# Battery_18650_3.net
KiCad netlist of a schematic drawn in EasyEDA Pro
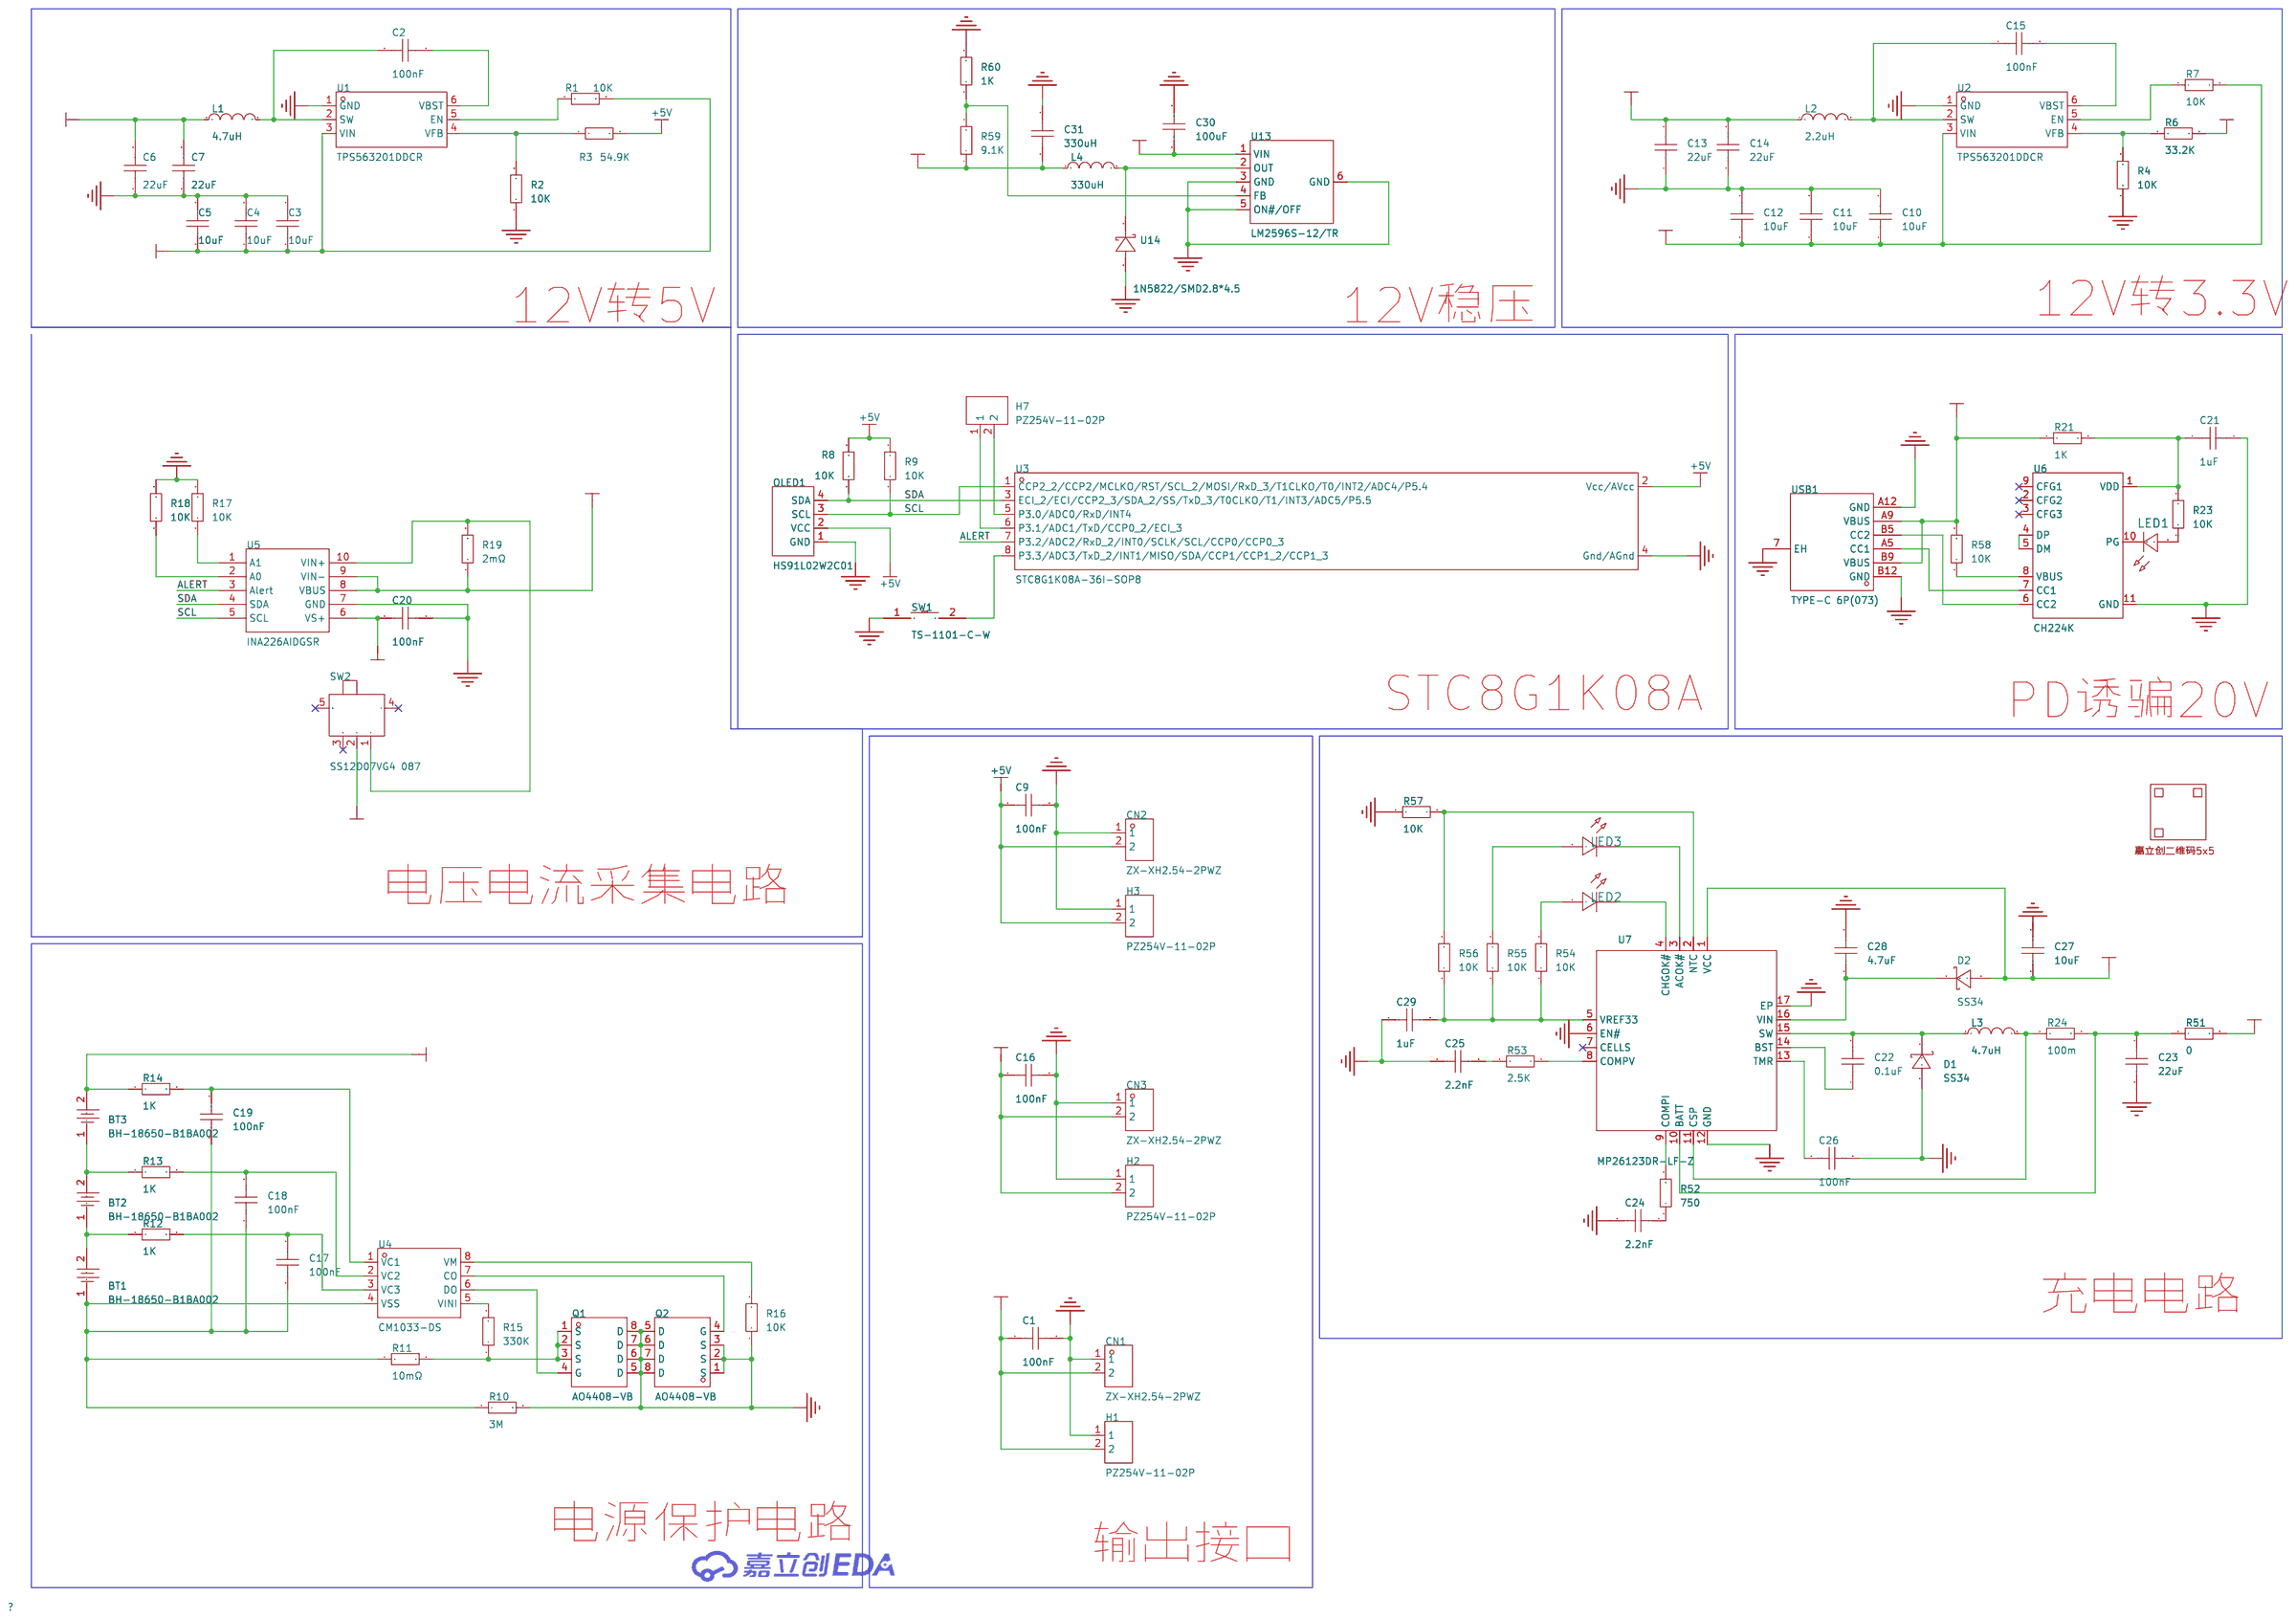
[diagram p0: schematic sheet]

(export (version "E")
  (design (tool "Eeschema 10.0.6"))
  (components
    (comp (ref "BT1")
      (value "BH-18650-B1BA002")
      (footprint "easyedapro:BATTERY-SMD_18650-1S-L77.1-W20.7-1")
      (description "连接器类型:电池盒;适用电池规格:18650;")
      (fields (field (name "Manufacturer") "MYOUNG(美阳)"))
      (libsource (lib "easyedapro") (part "BH-18650-B1BA002"))
    )
    (comp (ref "BT2")
      (value "BH-18650-B1BA002")
      (footprint "easyedapro:BATTERY-SMD_18650-1S-L77.1-W20.7-1")
      (description "连接器类型:电池盒;适用电池规格:18650;")
      (fields (field (name "Manufacturer") "MYOUNG(美阳)"))
      (libsource (lib "easyedapro") (part "BH-18650-B1BA002"))
    )
    (comp (ref "BT3")
      (value "BH-18650-B1BA002")
      (footprint "easyedapro:BATTERY-SMD_18650-1S-L77.1-W20.7-1")
      (description "连接器类型:电池盒;适用电池规格:18650;")
      (fields (field (name "Manufacturer") "MYOUNG(美阳)"))
      (libsource (lib "easyedapro") (part "BH-18650-B1BA002"))
    )
    (comp (ref "C1")
      (value "100nF")
      (footprint "easyedapro:C0603")
      (libsource (lib "easyedapro") (part "CapAcitance"))
    )
    (comp (ref "C2")
      (value "100nF")
      (footprint "easyedapro:C0603")
      (libsource (lib "easyedapro") (part "CapAcitance"))
    )
    (comp (ref "C3")
      (value "10uF")
      (footprint "easyedapro:C0603")
      (libsource (lib "easyedapro") (part "CapAcitance"))
    )
    (comp (ref "C4")
      (value "10uF")
      (footprint "easyedapro:C0603")
      (libsource (lib "easyedapro") (part "CapAcitance"))
    )
    (comp (ref "C5")
      (value "10uF")
      (footprint "easyedapro:C0603")
      (libsource (lib "easyedapro") (part "CapAcitance"))
    )
    (comp (ref "C6")
      (value "22uF")
      (footprint "easyedapro:C0603")
      (libsource (lib "easyedapro") (part "CapAcitance"))
    )
    (comp (ref "C7")
      (value "22uF")
      (footprint "easyedapro:C0603")
      (libsource (lib "easyedapro") (part "CapAcitance"))
    )
    (comp (ref "C9")
      (value "100nF")
      (footprint "easyedapro:C0603")
      (libsource (lib "easyedapro") (part "CapAcitance"))
    )
    (comp (ref "C10")
      (value "10uF")
      (footprint "easyedapro:C0603")
      (libsource (lib "easyedapro") (part "CapAcitance"))
    )
    (comp (ref "C11")
      (value "10uF")
      (footprint "easyedapro:C0603")
      (libsource (lib "easyedapro") (part "CapAcitance"))
    )
    (comp (ref "C12")
      (value "10uF")
      (footprint "easyedapro:C0603")
      (libsource (lib "easyedapro") (part "CapAcitance"))
    )
    (comp (ref "C13")
      (value "22uF")
      (footprint "easyedapro:C0603")
      (libsource (lib "easyedapro") (part "CapAcitance"))
    )
    (comp (ref "C14")
      (value "22uF")
      (footprint "easyedapro:C0603")
      (libsource (lib "easyedapro") (part "CapAcitance"))
    )
    (comp (ref "C15")
      (value "100nF")
      (footprint "easyedapro:C0603")
      (libsource (lib "easyedapro") (part "CapAcitance"))
    )
    (comp (ref "C16")
      (value "100nF")
      (footprint "easyedapro:C0603")
      (libsource (lib "easyedapro") (part "CapAcitance"))
    )
    (comp (ref "C17")
      (value "100nF")
      (footprint "easyedapro:C0603")
      (libsource (lib "easyedapro") (part "CapAcitance"))
    )
    (comp (ref "C18")
      (value "100nF")
      (footprint "easyedapro:C0603")
      (libsource (lib "easyedapro") (part "CapAcitance"))
    )
    (comp (ref "C19")
      (value "100nF")
      (footprint "easyedapro:C0603")
      (libsource (lib "easyedapro") (part "CapAcitance"))
    )
    (comp (ref "C20")
      (value "100nF")
      (footprint "easyedapro:C0603")
      (libsource (lib "easyedapro") (part "CapAcitance"))
    )
    (comp (ref "C21")
      (value "1uF")
      (footprint "easyedapro:C0603")
      (libsource (lib "easyedapro") (part "CapAcitance"))
    )
    (comp (ref "C22")
      (value "0.1uF")
      (footprint "easyedapro:C0603")
      (libsource (lib "easyedapro") (part "CapAcitance"))
    )
    (comp (ref "C23")
      (value "22uF")
      (footprint "easyedapro:C0603")
      (libsource (lib "easyedapro") (part "CapAcitance"))
    )
    (comp (ref "C24")
      (value "2.2nF")
      (footprint "easyedapro:C0603")
      (libsource (lib "easyedapro") (part "CapAcitance"))
    )
    (comp (ref "C25")
      (value "2.2nF")
      (footprint "easyedapro:C0603")
      (libsource (lib "easyedapro") (part "CapAcitance"))
    )
    (comp (ref "C26")
      (value "100nF")
      (footprint "easyedapro:C0603")
      (libsource (lib "easyedapro") (part "CapAcitance"))
    )
    (comp (ref "C27")
      (value "10uF")
      (footprint "easyedapro:C0603")
      (libsource (lib "easyedapro") (part "CapAcitance"))
    )
    (comp (ref "C28")
      (value "4.7uF")
      (footprint "easyedapro:C0603")
      (libsource (lib "easyedapro") (part "CapAcitance"))
    )
    (comp (ref "C29")
      (value "1uF")
      (footprint "easyedapro:C0603")
      (libsource (lib "easyedapro") (part "CapAcitance"))
    )
    (comp (ref "C30")
      (value "100uF")
      (footprint "easyedapro:C0603")
      (libsource (lib "easyedapro") (part "CapAcitance"))
    )
    (comp (ref "C31")
      (value "330uH")
      (footprint "easyedapro:C0603")
      (libsource (lib "easyedapro") (part "CapAcitance"))
    )
    (comp (ref "CN1")
      (value "ZX-XH2.54-2PWZ")
      (footprint "easyedapro:CONN-TH_2P-P2.50_ZX-XH2.54-2PWZ")
      (fields (field (name "Manufacturer") "Megastar(兆星)"))
      (libsource (lib "easyedapro") (part "ZX-XH2.54-2PWZ"))
    )
    (comp (ref "CN2")
      (value "ZX-XH2.54-2PWZ")
      (footprint "easyedapro:CONN-TH_2P-P2.50_ZX-XH2.54-2PWZ")
      (fields (field (name "Manufacturer") "Megastar(兆星)"))
      (libsource (lib "easyedapro") (part "ZX-XH2.54-2PWZ"))
    )
    (comp (ref "CN3")
      (value "ZX-XH2.54-2PWZ")
      (footprint "easyedapro:CONN-TH_2P-P2.50_ZX-XH2.54-2PWZ")
      (fields (field (name "Manufacturer") "Megastar(兆星)"))
      (libsource (lib "easyedapro") (part "ZX-XH2.54-2PWZ"))
    )
    (comp (ref "D1")
      (value "SS34")
      (footprint "easyedapro:SMC_L6.9-W5.9-LS7.9-RD")
      (description "正向压降(Vf):500mV@3A;直流反向耐压(Vr):40V;平均整流电流(Io):3A;")
      (fields (field (name "Manufacturer") "onsemi(安森美)"))
      (libsource (lib "easyedapro") (part "SS34_C154551"))
    )
    (comp (ref "D2")
      (value "SS34")
      (footprint "easyedapro:SMC_L6.9-W5.9-LS7.9-RD")
      (description "正向压降(Vf):500mV@3A;直流反向耐压(Vr):40V;平均整流电流(Io):3A;")
      (fields (field (name "Manufacturer") "onsemi(安森美)"))
      (libsource (lib "easyedapro") (part "SS34_C154551"))
    )
    (comp (ref "H1")
      (value "PZ254V-11-02P")
      (footprint "easyedapro:HDR-TH_2P-P2.54-V-M")
      (fields (field (name "Manufacturer") "XFCN(兴飞)"))
      (libsource (lib "easyedapro") (part "PZ254V-11-02P"))
    )
    (comp (ref "H2")
      (value "PZ254V-11-02P")
      (footprint "easyedapro:HDR-TH_2P-P2.54-V-M")
      (fields (field (name "Manufacturer") "XFCN(兴飞)"))
      (libsource (lib "easyedapro") (part "PZ254V-11-02P"))
    )
    (comp (ref "H3")
      (value "PZ254V-11-02P")
      (footprint "easyedapro:HDR-TH_2P-P2.54-V-M")
      (fields (field (name "Manufacturer") "XFCN(兴飞)"))
      (libsource (lib "easyedapro") (part "PZ254V-11-02P"))
    )
    (comp (ref "H7")
      (value "PZ254V-11-02P")
      (footprint "easyedapro:HDR-TH_2P-P2.54-V-M")
      (fields (field (name "Manufacturer") "XFCN(兴飞)"))
      (libsource (lib "easyedapro") (part "PZ254V-11-02P"))
    )
    (comp (ref "L1")
      (value "4.7uH")
      (footprint "easyedapro:IND-SMD_L4.0-W4.0_FNR40XXS")
      (description "电感值:4.7uH;精度:±20%;额定电流:2.3A;饱和电流(Isat):3.2A;类型:磁胶屏蔽绕线合金电感;")
      (fields (field (name "Manufacturer Part") "FNR4030S4R7MT") (field (name "Manufacturer") "cjiang(长江微电)"))
      (libsource (lib "easyedapro") (part "FNR4030S4R7MT"))
    )
    (comp (ref "L2")
      (value "2.2uH")
      (footprint "easyedapro:IND-SMD_L4.0-W4.0_FNR40XXS")
      (description "电感值:4.7uH;精度:±20%;额定电流:2.3A;饱和电流(Isat):3.2A;类型:磁胶屏蔽绕线合金电感;")
      (fields (field (name "Manufacturer Part") "FNR4030S4R7MT") (field (name "Manufacturer") "cjiang(长江微电)"))
      (libsource (lib "easyedapro") (part "FNR4030S4R7MT"))
    )
    (comp (ref "L3")
      (value "4.7uH")
      (footprint "easyedapro:IND-SMD_L11.5-W10.0_FXL1040")
      (description "电感值:4.7uH;精度:±20%;额定电流:9A;饱和电流(Isat):15A;类型:一体成型电感;")
      (fields (field (name "Manufacturer Part") "FXL1040-4R7-M") (field (name "Manufacturer") "cjiang(长江微电)"))
      (libsource (lib "easyedapro") (part "FXL1040-4R7-M"))
    )
    (comp (ref "L4")
      (value "330uH")
      (footprint "easyedapro:IND-SMD_L11.5-W10.0_FXL1040")
      (description "电感值:4.7uH;精度:±20%;额定电流:9A;饱和电流(Isat):15A;类型:一体成型电感;")
      (fields (field (name "Manufacturer Part") "FXL1040-4R7-M") (field (name "Manufacturer") "cjiang(长江微电)"))
      (libsource (lib "easyedapro") (part "FXL1040-4R7-M"))
    )
    (comp (ref "LED1")
      (value "~")
      (footprint "easyedapro:LED_0603")
      (libsource (lib "easyedapro") (part "LED_R"))
    )
    (comp (ref "LED2")
      (value "~")
      (footprint "easyedapro:LED_0603")
      (libsource (lib "easyedapro") (part "LED_R"))
    )
    (comp (ref "LED3")
      (value "~")
      (footprint "easyedapro:LED_0603")
      (libsource (lib "easyedapro") (part "LED_R"))
    )
    (comp (ref "OLED1")
      (value "HS91L02W2C01")
      (footprint "easyedapro:OLED-TH_L38.0-W12.0_HS91L02W2C01")
      (description "主控芯片:SSD1306;接口类型:I2C;尺寸(inch):0.91;像素分辨率:128x32;")
      (fields (field (name "Manufacturer") "HS(汉昇)"))
      (libsource (lib "easyedapro") (part "HS91L02W2C01"))
    )
    (comp (ref "Q1")
      (value "AO4408-VB")
      (footprint "easyedapro:SO-8_L4.9-W3.9-P1.27-LS5.9-BL")
      (description "类型:1个N沟道;漏源电压(Vdss):20V;连续漏极电流(Id):13A;导通电阻(RDS(on)@Vgs,Id):-;功率:2.2W;阈值电压(Vgs(th)@Id):1V@250uA;")
      (fields (field (name "Manufacturer") "VBsemi(微碧半导体)"))
      (libsource (lib "easyedapro") (part "AO4408"))
    )
    (comp (ref "Q2")
      (value "AO4408-VB")
      (footprint "easyedapro:SO-8_L4.9-W3.9-P1.27-LS5.9-BL")
      (description "类型:1个N沟道;漏源电压(Vdss):20V;连续漏极电流(Id):13A;导通电阻(RDS(on)@Vgs,Id):-;功率:2.2W;阈值电压(Vgs(th)@Id):1V@250uA;")
      (fields (field (name "Manufacturer") "VBsemi(微碧半导体)"))
      (libsource (lib "easyedapro") (part "AO4408"))
    )
    (comp (ref "R1") (value "10K") (footprint "easyedapro:R0603") (libsource (lib "easyedapro") (part "电阻")))
    (comp (ref "R2") (value "10K") (footprint "easyedapro:R0603") (libsource (lib "easyedapro") (part "电阻")))
    (comp (ref "R3")
      (value "54.9K")
      (footprint "easyedapro:R0603")
      (libsource (lib "easyedapro") (part "电阻"))
    )
    (comp (ref "R4") (value "10K") (footprint "easyedapro:R0603") (libsource (lib "easyedapro") (part "电阻")))
    (comp (ref "R6")
      (value "33.2K")
      (footprint "easyedapro:R0603")
      (libsource (lib "easyedapro") (part "电阻"))
    )
    (comp (ref "R7") (value "10K") (footprint "easyedapro:R0603") (libsource (lib "easyedapro") (part "电阻")))
    (comp (ref "R8") (value "10K") (footprint "easyedapro:R0603") (libsource (lib "easyedapro") (part "电阻")))
    (comp (ref "R9") (value "10K") (footprint "easyedapro:R0603") (libsource (lib "easyedapro") (part "电阻")))
    (comp (ref "R10") (value "3M") (footprint "easyedapro:R0603") (libsource (lib "easyedapro") (part "电阻")))
    (comp (ref "R11")
      (value "10mΩ")
      (footprint "easyedapro:R0603")
      (libsource (lib "easyedapro") (part "电阻"))
    )
    (comp (ref "R12") (value "1K") (footprint "easyedapro:R0603") (libsource (lib "easyedapro") (part "电阻")))
    (comp (ref "R13") (value "1K") (footprint "easyedapro:R0603") (libsource (lib "easyedapro") (part "电阻")))
    (comp (ref "R14") (value "1K") (footprint "easyedapro:R0603") (libsource (lib "easyedapro") (part "电阻")))
    (comp (ref "R15")
      (value "330K")
      (footprint "easyedapro:R0603")
      (libsource (lib "easyedapro") (part "电阻"))
    )
    (comp (ref "R16") (value "10K") (footprint "easyedapro:R0603") (libsource (lib "easyedapro") (part "电阻")))
    (comp (ref "R17") (value "10K") (footprint "easyedapro:R0603") (libsource (lib "easyedapro") (part "电阻")))
    (comp (ref "R18") (value "10K") (footprint "easyedapro:R0603") (libsource (lib "easyedapro") (part "电阻")))
    (comp (ref "R19") (value "2mΩ") (footprint "easyedapro:R0603") (libsource (lib "easyedapro") (part "电阻")))
    (comp (ref "R21") (value "1K") (footprint "easyedapro:R0603") (libsource (lib "easyedapro") (part "电阻")))
    (comp (ref "R23") (value "10K") (footprint "easyedapro:R0603") (libsource (lib "easyedapro") (part "电阻")))
    (comp (ref "R24")
      (value "100m")
      (footprint "easyedapro:R0603")
      (libsource (lib "easyedapro") (part "电阻"))
    )
    (comp (ref "R51") (value "0") (footprint "easyedapro:R0603") (libsource (lib "easyedapro") (part "电阻")))
    (comp (ref "R52") (value "750") (footprint "easyedapro:R0603") (libsource (lib "easyedapro") (part "电阻")))
    (comp (ref "R53")
      (value "2.5K")
      (footprint "easyedapro:R0603")
      (libsource (lib "easyedapro") (part "电阻"))
    )
    (comp (ref "R54") (value "10K") (footprint "easyedapro:R0603") (libsource (lib "easyedapro") (part "电阻")))
    (comp (ref "R55") (value "10K") (footprint "easyedapro:R0603") (libsource (lib "easyedapro") (part "电阻")))
    (comp (ref "R56") (value "10K") (footprint "easyedapro:R0603") (libsource (lib "easyedapro") (part "电阻")))
    (comp (ref "R57") (value "10K") (footprint "easyedapro:R0603") (libsource (lib "easyedapro") (part "电阻")))
    (comp (ref "R58") (value "10K") (footprint "easyedapro:R0603") (libsource (lib "easyedapro") (part "电阻")))
    (comp (ref "R59")
      (value "9.1K")
      (footprint "easyedapro:R0603")
      (libsource (lib "easyedapro") (part "电阻"))
    )
    (comp (ref "R60") (value "1K") (footprint "easyedapro:R0603") (libsource (lib "easyedapro") (part "电阻")))
    (comp (ref "SW1")
      (value "TS-1101-C-W")
      (footprint "easyedapro:SW-SMD_L6.0-W3.3-LS8.0")
      (fields (field (name "Manufacturer") "XKB Connectivity(中国星坤)"))
      (libsource (lib "easyedapro") (part "TS-1101-C-W"))
    )
    (comp (ref "SW2")
      (value "SS12D07VG4 087")
      (footprint "easyedapro:SW-TH_SS12D07VG4")
      (description "电路结构:单刀双掷;安装方式:直插;开关颜色:-;额定电流(DC):500mA;额定电压(DC):50V;额定电流(AC):-;额定电压(AC):-;机械寿命:5千次;")
      (fields (field (name "Manufacturer") "SHOU HAN(首韩)"))
      (libsource (lib "easyedapro") (part "SS12D07VG4 087"))
    )
    (comp (ref "U1")
      (value "TPS563201DDCR")
      (footprint "easyedapro:SOT-23-6_L2.9-W1.6-P0.95-LS2.8-BR")
      (description "功能类型:降压型;输出类型:可调;工作电压:4.5V~17V;输出电压:768mV~7V;输出电流:3A;")
      (fields (field (name "Manufacturer") "TI(德州仪器)"))
      (libsource (lib "easyedapro") (part "TPS563201DDCR"))
    )
    (comp (ref "U2")
      (value "TPS563201DDCR")
      (footprint "easyedapro:SOT-23-6_L2.9-W1.6-P0.95-LS2.8-BR")
      (description "功能类型:降压型;输出类型:可调;工作电压:4.5V~17V;输出电压:768mV~7V;输出电流:3A;")
      (fields (field (name "Manufacturer") "TI(德州仪器)"))
      (libsource (lib "easyedapro") (part "TPS563201DDCR"))
    )
    (comp (ref "U3")
      (value "STC8G1K08A-36I-SOP8")
      (footprint "easyedapro:SOP-8_L5.0-W4.0-P1.27-LS6.0-BL")
      (description "CPU内核:51系列;应用领域:-;")
      (fields (field (name "Manufacturer") "STC"))
      (libsource (lib "easyedapro") (part "STC8G1K08A-36I-SOP8"))
    )
    (comp (ref "U4")
      (value "CM1033-DS")
      (footprint "easyedapro:SOP-8_L5.0-W4.0-P1.27-LS6.2-BL")
      (fields (field (name "Manufacturer") "iCM(创芯微)"))
      (libsource (lib "easyedapro") (part "CM1033-DS"))
    )
    (comp (ref "U5")
      (value "INA226AIDGSR")
      (footprint "easyedapro:MSOP-10_L3.0-W3.0-P0.50-LS5.0-BL")
      (description "放大器数:-;共模电压:300mV~40V;增益:-;带宽:-;")
      (fields (field (name "Manufacturer") "TI(德州仪器)"))
      (libsource (lib "easyedapro") (part "INA226AIDGSR"))
    )
    (comp (ref "U6")
      (value "CH224K")
      (footprint "easyedapro:ESSOP-10_L4.9-W3.9-P1.0-LS6.0-TL-EP")
      (fields (field (name "Manufacturer") "WCH(南京沁恒)"))
      (libsource (lib "easyedapro") (part "CH224K"))
    )
    (comp (ref "U7")
      (value "MP26123DR-LF-Z")
      (footprint "easyedapro:QFN-16_L4.0-W4.0-P0.65-BL-EP2.2")
      (description "电源电压:24V;最大充电电流:2A;电池类型:锂离子/聚合物;电池节数:2~3;")
      (fields (field (name "Manufacturer") "MPS(芯源)"))
      (libsource (lib "easyedapro") (part "MP26123DR-LF-Z"))
    )
    (comp (ref "U13")
      (value "LM2596S-12/TR")
      (footprint "easyedapro:TO-263-5_L10.6-W9.6-P1.70-LS15.9-BR")
      (description "功能类型:降压型;工作电压:4.5V~40V;输出电压:11.52V~12.48V;输出电流:3A;")
      (fields (field (name "Manufacturer") "HGC(华冠)"))
      (libsource (lib "easyedapro") (part "LM2596S-12/TR_C462059"))
    )
    (comp (ref "U14")
      (value "1N5822/SMD2.8*4.5")
      (footprint "easyedapro:DO-214AC_L4.3-W2.7-LS5.0-RD")
      (libsource (lib "easyedapro") (part "1N5822/SMD2.8*4.5"))
    )
    (comp (ref "U24")
      (value "~")
      (footprint "easyedapro:JLC-QRCODE-5x5")
      (libsource (lib "easyedapro") (part "嘉立创二维码5x5"))
    )
    (comp (ref "USB1")
      (value "TYPE-C 6P(073)")
      (footprint "easyedapro:TYPE-C-SMD_TYPE-C-6P_5")
      (description "连接器类型:Type-C;标准:USB 3.1;公母:母;安装方式:卧贴;触点数量:6P;端口数量:1;额定电流 - 电源:3A;工作温度范围:-25°C~+85°C;")
      (fields (field (name "Manufacturer") "SHOU HAN(首韩)"))
      (libsource (lib "easyedapro") (part "TYPE-C 6P(073)"))
    )
  )
  (nets
    (net (code "1") (name "+3.3V") (class "Default")
      (node (ref "C13") (pin "2") (pinfunction "2_2") (pintype "input"))
      (node (ref "C14") (pin "2") (pinfunction "2_2") (pintype "input"))
      (node (ref "C16") (pin "1") (pinfunction "1_1") (pintype "input"))
      (node (ref "C20") (pin "1") (pinfunction "1_1") (pintype "input"))
      (node (ref "CN3") (pin "2") (pinfunction "2_2") (pintype "unspecified"))
      (node (ref "H2") (pin "2") (pinfunction "2_2") (pintype "unspecified"))
      (node (ref "L2") (pin "1") (pinfunction "1_1") (pintype "unspecified"))
      (node (ref "R6") (pin "2") (pinfunction "2_2") (pintype "input"))
      (node (ref "U5") (pin "6") (pinfunction "VS+_6") (pintype "unspecified"))
    )
    (net (code "2") (name "+5V") (class "Default")
      (node (ref "C6") (pin "2") (pinfunction "2_2") (pintype "input"))
      (node (ref "C7") (pin "2") (pinfunction "2_2") (pintype "input"))
      (node (ref "C9") (pin "1") (pinfunction "1_1") (pintype "input"))
      (node (ref "CN2") (pin "2") (pinfunction "2_2") (pintype "unspecified"))
      (node (ref "H3") (pin "2") (pinfunction "2_2") (pintype "unspecified"))
      (node (ref "L1") (pin "1") (pinfunction "1_1") (pintype "unspecified"))
      (node (ref "OLED1") (pin "2") (pinfunction "VCC_2") (pintype "unspecified"))
      (node (ref "R3") (pin "2") (pinfunction "2_2") (pintype "input"))
      (node (ref "R8") (pin "2") (pinfunction "2_2") (pintype "input"))
      (node (ref "R9") (pin "1") (pinfunction "1_1") (pintype "input"))
      (node (ref "U3") (pin "2") (pinfunction "Vcc/AVcc_2") (pintype "unspecified"))
    )
    (net (code "3") (name "/ALERT") (class "Default")
      (node (ref "U3") (pin "7") (pinfunction "P3.2/ADC2/RxD_2/INT0/SCLK/SCL/CCP0/CCP0_3_7") (pintype "unspecified"))
      (node (ref "U5") (pin "3") (pinfunction "Alert_3") (pintype "unspecified"))
    )
    (net (code "4") (name "/SCL") (class "Default")
      (node (ref "OLED1") (pin "3") (pinfunction "SCL_3") (pintype "unspecified"))
      (node (ref "R9") (pin "2") (pinfunction "2_2") (pintype "input"))
      (node (ref "U3") (pin "1") (pinfunction "CCP2_2/CCP2/MCLKO/RST/SCL_2/MOSI/RxD_3/T1CLKO/T0/INT2/ADC4/P5.4_1") (pintype "unspecified"))
      (node (ref "U5") (pin "5") (pinfunction "SCL_5") (pintype "unspecified"))
    )
    (net (code "5") (name "/SDA") (class "Default")
      (node (ref "OLED1") (pin "4") (pinfunction "SDA_4") (pintype "unspecified"))
      (node (ref "R8") (pin "1") (pinfunction "1_1") (pintype "input"))
      (node (ref "U3") (pin "3") (pinfunction "ECI_2/ECI/CCP2_3/SDA_2/SS/TxD_3/T0CLKO/T1/INT3/ADC5/P5.5_3") (pintype "unspecified"))
      (node (ref "U5") (pin "4") (pinfunction "SDA_4") (pintype "unspecified"))
    )
    (net (code "6") (name "12V") (class "Default")
      (node (ref "C1") (pin "1") (pinfunction "1_1") (pintype "input"))
      (node (ref "C31") (pin "1") (pinfunction "1_1") (pintype "input"))
      (node (ref "CN1") (pin "2") (pinfunction "2_2") (pintype "unspecified"))
      (node (ref "H1") (pin "2") (pinfunction "2_2") (pintype "unspecified"))
      (node (ref "L4") (pin "1") (pinfunction "1_1") (pintype "unspecified"))
      (node (ref "R59") (pin "1") (pinfunction "1_1") (pintype "input"))
    )
    (net (code "7") (name "GND") (class "Default")
      (node (ref "C1") (pin "2") (pinfunction "2_2") (pintype "input"))
      (node (ref "C10") (pin "2") (pinfunction "2_2") (pintype "input"))
      (node (ref "C11") (pin "2") (pinfunction "2_2") (pintype "input"))
      (node (ref "C12") (pin "2") (pinfunction "2_2") (pintype "input"))
      (node (ref "C13") (pin "1") (pinfunction "1_1") (pintype "input"))
      (node (ref "C14") (pin "1") (pinfunction "1_1") (pintype "input"))
      (node (ref "C16") (pin "2") (pinfunction "2_2") (pintype "input"))
      (node (ref "C20") (pin "2") (pinfunction "2_2") (pintype "input"))
      (node (ref "C21") (pin "2") (pinfunction "2_2") (pintype "input"))
      (node (ref "C23") (pin "2") (pinfunction "2_2") (pintype "input"))
      (node (ref "C24") (pin "2") (pinfunction "2_2") (pintype "input"))
      (node (ref "C25") (pin "1") (pinfunction "1_1") (pintype "input"))
      (node (ref "C26") (pin "2") (pinfunction "2_2") (pintype "input"))
      (node (ref "C27") (pin "2") (pinfunction "2_2") (pintype "input"))
      (node (ref "C28") (pin "2") (pinfunction "2_2") (pintype "input"))
      (node (ref "C29") (pin "1") (pinfunction "1_1") (pintype "input"))
      (node (ref "C3") (pin "2") (pinfunction "2_2") (pintype "input"))
      (node (ref "C30") (pin "2") (pinfunction "2_2") (pintype "input"))
      (node (ref "C31") (pin "2") (pinfunction "2_2") (pintype "input"))
      (node (ref "C4") (pin "2") (pinfunction "2_2") (pintype "input"))
      (node (ref "C5") (pin "2") (pinfunction "2_2") (pintype "input"))
      (node (ref "C6") (pin "1") (pinfunction "1_1") (pintype "input"))
      (node (ref "C7") (pin "1") (pinfunction "1_1") (pintype "input"))
      (node (ref "C9") (pin "2") (pinfunction "2_2") (pintype "input"))
      (node (ref "CN1") (pin "1") (pinfunction "1_1") (pintype "unspecified"))
      (node (ref "CN2") (pin "1") (pinfunction "1_1") (pintype "unspecified"))
      (node (ref "CN3") (pin "1") (pinfunction "1_1") (pintype "unspecified"))
      (node (ref "D1") (pin "2") (pinfunction "A_2") (pintype "unspecified"))
      (node (ref "H1") (pin "1") (pinfunction "1_1") (pintype "unspecified"))
      (node (ref "H2") (pin "1") (pinfunction "1_1") (pintype "unspecified"))
      (node (ref "H3") (pin "1") (pinfunction "1_1") (pintype "unspecified"))
      (node (ref "OLED1") (pin "1") (pinfunction "GND_1") (pintype "unspecified"))
      (node (ref "Q1") (pin "5") (pinfunction "D_5") (pintype "unspecified"))
      (node (ref "Q1") (pin "6") (pinfunction "D_6") (pintype "unspecified"))
      (node (ref "Q1") (pin "7") (pinfunction "D_7") (pintype "unspecified"))
      (node (ref "Q1") (pin "8") (pinfunction "D_8") (pintype "unspecified"))
      (node (ref "Q2") (pin "1") (pinfunction "S_1") (pintype "unspecified"))
      (node (ref "Q2") (pin "2") (pinfunction "S_2") (pintype "unspecified"))
      (node (ref "Q2") (pin "3") (pinfunction "S_3") (pintype "unspecified"))
      (node (ref "Q2") (pin "5") (pinfunction "D_5") (pintype "unspecified"))
      (node (ref "Q2") (pin "6") (pinfunction "D_6") (pintype "unspecified"))
      (node (ref "Q2") (pin "7") (pinfunction "D_7") (pintype "unspecified"))
      (node (ref "Q2") (pin "8") (pinfunction "D_8") (pintype "unspecified"))
      (node (ref "R10") (pin "2") (pinfunction "2_2") (pintype "input"))
      (node (ref "R16") (pin "1") (pinfunction "1_1") (pintype "input"))
      (node (ref "R17") (pin "2") (pinfunction "2_2") (pintype "input"))
      (node (ref "R18") (pin "2") (pinfunction "2_2") (pintype "input"))
      (node (ref "R2") (pin "1") (pinfunction "1_1") (pintype "input"))
      (node (ref "R4") (pin "1") (pinfunction "1_1") (pintype "input"))
      (node (ref "R57") (pin "2") (pinfunction "2_2") (pintype "input"))
      (node (ref "R60") (pin "2") (pinfunction "2_2") (pintype "input"))
      (node (ref "SW1") (pin "1") (pinfunction "1_1") (pintype "unspecified"))
      (node (ref "U1") (pin "1") (pinfunction "GND_1") (pintype "unspecified"))
      (node (ref "U13") (pin "3") (pinfunction "GND_3") (pintype "unspecified"))
      (node (ref "U13") (pin "5") (pinfunction "ON#/OFF_5") (pintype "unspecified"))
      (node (ref "U13") (pin "6") (pinfunction "GND_6") (pintype "unspecified"))
      (node (ref "U14") (pin "2") (pinfunction "K_2") (pintype "unspecified"))
      (node (ref "U2") (pin "1") (pinfunction "GND_1") (pintype "unspecified"))
      (node (ref "U3") (pin "4") (pinfunction "Gnd/AGnd_4") (pintype "unspecified"))
      (node (ref "U5") (pin "7") (pinfunction "GND_7") (pintype "unspecified"))
      (node (ref "U6") (pin "11") (pinfunction "GND_11") (pintype "unspecified"))
      (node (ref "U7") (pin "12") (pinfunction "GND_12") (pintype "unspecified"))
      (node (ref "U7") (pin "17") (pinfunction "EP_17") (pintype "unspecified"))
      (node (ref "U7") (pin "6") (pinfunction "EN#_6") (pintype "unspecified"))
      (node (ref "USB1") (pin "7") (pinfunction "EH_7") (pintype "unspecified"))
      (node (ref "USB1") (pin "A12") (pinfunction "GND_A12") (pintype "unspecified"))
      (node (ref "USB1") (pin "B12") (pinfunction "GND_B12") (pintype "unspecified"))
    )
    (net (code "8") (name "Net-(BT1-Pad2)") (class "Default")
      (node (ref "BT1") (pin "2") (pinfunction "2_2") (pintype "input"))
      (node (ref "BT2") (pin "1") (pinfunction "1_1") (pintype "input"))
      (node (ref "R12") (pin "1") (pinfunction "1_1") (pintype "input"))
    )
    (net (code "9") (name "Net-(BT2-Pad2)") (class "Default")
      (node (ref "BT2") (pin "2") (pinfunction "2_2") (pintype "input"))
      (node (ref "BT3") (pin "1") (pinfunction "1_1") (pintype "input"))
      (node (ref "R13") (pin "1") (pinfunction "1_1") (pintype "input"))
    )
    (net (code "10") (name "Net-(C24-Pad1)") (class "Default")
      (node (ref "C24") (pin "1") (pinfunction "1_1") (pintype "input"))
      (node (ref "R52") (pin "1") (pinfunction "1_1") (pintype "input"))
    )
    (net (code "11") (name "Net-(C25-Pad2)") (class "Default")
      (node (ref "C25") (pin "2") (pinfunction "2_2") (pintype "input"))
      (node (ref "R53") (pin "1") (pinfunction "1_1") (pintype "input"))
    )
    (net (code "12") (name "Net-(D1-C)") (class "Default")
      (node (ref "C22") (pin "2") (pinfunction "2_2") (pintype "input"))
      (node (ref "D1") (pin "1") (pinfunction "C_1") (pintype "unspecified"))
      (node (ref "L3") (pin "1") (pinfunction "1_1") (pintype "unspecified"))
      (node (ref "U7") (pin "15") (pinfunction "SW_15") (pintype "unspecified"))
    )
    (net (code "13") (name "Net-(D2-C)") (class "Default")
      (node (ref "C28") (pin "1") (pinfunction "1_1") (pintype "input"))
      (node (ref "D2") (pin "1") (pinfunction "C_1") (pintype "unspecified"))
      (node (ref "U7") (pin "16") (pinfunction "VIN_16") (pintype "unspecified"))
    )
    (net (code "14") (name "Net-(LED1-A)") (class "Default")
      (node (ref "LED1") (pin "2") (pinfunction "A_2") (pintype "input"))
      (node (ref "R23") (pin "1") (pinfunction "1_1") (pintype "input"))
    )
    (net (code "15") (name "Net-(LED1-C)") (class "Default")
      (node (ref "LED1") (pin "1") (pinfunction "C_1") (pintype "input"))
      (node (ref "U6") (pin "10") (pinfunction "PG_10") (pintype "unspecified"))
    )
    (net (code "16") (name "Net-(LED2-A)") (class "Default")
      (node (ref "LED2") (pin "2") (pinfunction "A_2") (pintype "input"))
      (node (ref "R54") (pin "2") (pinfunction "2_2") (pintype "input"))
    )
    (net (code "17") (name "Net-(LED2-C)") (class "Default")
      (node (ref "LED2") (pin "1") (pinfunction "C_1") (pintype "input"))
      (node (ref "U7") (pin "4") (pinfunction "CHGOK#_4") (pintype "unspecified"))
    )
    (net (code "18") (name "Net-(LED3-A)") (class "Default")
      (node (ref "LED3") (pin "2") (pinfunction "A_2") (pintype "input"))
      (node (ref "R55") (pin "2") (pinfunction "2_2") (pintype "input"))
    )
    (net (code "19") (name "Net-(LED3-C)") (class "Default")
      (node (ref "LED3") (pin "1") (pinfunction "C_1") (pintype "input"))
      (node (ref "U7") (pin "3") (pinfunction "ACOK#_3") (pintype "unspecified"))
    )
    (net (code "20") (name "Net-(Q1-G)") (class "Default")
      (node (ref "Q1") (pin "4") (pinfunction "G_4") (pintype "unspecified"))
      (node (ref "U4") (pin "6") (pinfunction "DO_6") (pintype "unspecified"))
    )
    (net (code "21") (name "Net-(Q1-S-Pad1)") (class "Default")
      (node (ref "Q1") (pin "1") (pinfunction "S_1") (pintype "unspecified"))
      (node (ref "Q1") (pin "2") (pinfunction "S_2") (pintype "unspecified"))
      (node (ref "Q1") (pin "3") (pinfunction "S_3") (pintype "unspecified"))
      (node (ref "R11") (pin "2") (pinfunction "2_2") (pintype "input"))
      (node (ref "R15") (pin "1") (pinfunction "1_1") (pintype "input"))
    )
    (net (code "22") (name "Net-(Q2-G)") (class "Default")
      (node (ref "Q2") (pin "4") (pinfunction "G_4") (pintype "unspecified"))
      (node (ref "U4") (pin "7") (pinfunction "CO_7") (pintype "unspecified"))
    )
    (net (code "23") (name "Net-(U1-EN)") (class "Default")
      (node (ref "R1") (pin "1") (pinfunction "1_1") (pintype "input"))
      (node (ref "U1") (pin "5") (pinfunction "EN_5") (pintype "unspecified"))
    )
    (net (code "24") (name "Net-(U1-SW)") (class "Default")
      (node (ref "C2") (pin "1") (pinfunction "1_1") (pintype "input"))
      (node (ref "L1") (pin "2") (pinfunction "2_2") (pintype "unspecified"))
      (node (ref "U1") (pin "2") (pinfunction "SW_2") (pintype "unspecified"))
    )
    (net (code "25") (name "Net-(U1-VBST)") (class "Default")
      (node (ref "C2") (pin "2") (pinfunction "2_2") (pintype "input"))
      (node (ref "U1") (pin "6") (pinfunction "VBST_6") (pintype "unspecified"))
    )
    (net (code "26") (name "Net-(U1-VFB)") (class "Default")
      (node (ref "R2") (pin "2") (pinfunction "2_2") (pintype "input"))
      (node (ref "R3") (pin "1") (pinfunction "1_1") (pintype "input"))
      (node (ref "U1") (pin "4") (pinfunction "VFB_4") (pintype "unspecified"))
    )
    (net (code "27") (name "Net-(U2-EN)") (class "Default")
      (node (ref "R7") (pin "1") (pinfunction "1_1") (pintype "input"))
      (node (ref "U2") (pin "5") (pinfunction "EN_5") (pintype "unspecified"))
    )
    (net (code "28") (name "Net-(U2-SW)") (class "Default")
      (node (ref "C15") (pin "1") (pinfunction "1_1") (pintype "input"))
      (node (ref "L2") (pin "2") (pinfunction "2_2") (pintype "unspecified"))
      (node (ref "U2") (pin "2") (pinfunction "SW_2") (pintype "unspecified"))
    )
    (net (code "29") (name "Net-(U2-VBST)") (class "Default")
      (node (ref "C15") (pin "2") (pinfunction "2_2") (pintype "input"))
      (node (ref "U2") (pin "6") (pinfunction "VBST_6") (pintype "unspecified"))
    )
    (net (code "30") (name "Net-(U2-VFB)") (class "Default")
      (node (ref "R4") (pin "2") (pinfunction "2_2") (pintype "input"))
      (node (ref "R6") (pin "1") (pinfunction "1_1") (pintype "input"))
      (node (ref "U2") (pin "4") (pinfunction "VFB_4") (pintype "unspecified"))
    )
    (net (code "31") (name "Net-(U3-P3.0{slash}ADC0{slash}RxD{slash}INT4)") (class "Default")
      (node (ref "H7") (pin "2") (pinfunction "2_2") (pintype "unspecified"))
      (node (ref "U3") (pin "5") (pinfunction "P3.0/ADC0/RxD/INT4_5") (pintype "unspecified"))
    )
    (net (code "32") (name "Net-(U3-P3.1{slash}ADC1{slash}TxD{slash}CCP0_2{slash}ECI_3)") (class "Default")
      (node (ref "H7") (pin "1") (pinfunction "1_1") (pintype "unspecified"))
      (node (ref "U3") (pin "6") (pinfunction "P3.1/ADC1/TxD/CCP0_2/ECI_3_6") (pintype "unspecified"))
    )
    (net (code "33") (name "Net-(U3-P3.3{slash}ADC3{slash}TxD_2{slash}INT1{slash}MISO{slash}SDA{slash}CCP1{slash}CCP1_2{slash}CCP1_3)") (class "Default")
      (node (ref "SW1") (pin "2") (pinfunction "2_2") (pintype "unspecified"))
      (node (ref "U3") (pin "8") (pinfunction "P3.3/ADC3/TxD_2/INT1/MISO/SDA/CCP1/CCP1_2/CCP1_3_8") (pintype "unspecified"))
    )
    (net (code "34") (name "Net-(U4-VC1)") (class "Default")
      (node (ref "C19") (pin "2") (pinfunction "2_2") (pintype "input"))
      (node (ref "R14") (pin "2") (pinfunction "2_2") (pintype "input"))
      (node (ref "U4") (pin "1") (pinfunction "VC1_1") (pintype "unspecified"))
    )
    (net (code "35") (name "Net-(U4-VC2)") (class "Default")
      (node (ref "C18") (pin "2") (pinfunction "2_2") (pintype "input"))
      (node (ref "R13") (pin "2") (pinfunction "2_2") (pintype "input"))
      (node (ref "U4") (pin "2") (pinfunction "VC2_2") (pintype "unspecified"))
    )
    (net (code "36") (name "Net-(U4-VC3)") (class "Default")
      (node (ref "C17") (pin "2") (pinfunction "2_2") (pintype "input"))
      (node (ref "R12") (pin "2") (pinfunction "2_2") (pintype "input"))
      (node (ref "U4") (pin "3") (pinfunction "VC3_3") (pintype "unspecified"))
    )
    (net (code "37") (name "Net-(U4-VINI)") (class "Default")
      (node (ref "R15") (pin "2") (pinfunction "2_2") (pintype "input"))
      (node (ref "U4") (pin "5") (pinfunction "VINI_5") (pintype "unspecified"))
    )
    (net (code "38") (name "Net-(U4-VM)") (class "Default")
      (node (ref "R16") (pin "2") (pinfunction "2_2") (pintype "input"))
      (node (ref "U4") (pin "8") (pinfunction "VM_8") (pintype "unspecified"))
    )
    (net (code "39") (name "Net-(U4-VSS)") (class "Default")
      (node (ref "BT1") (pin "1") (pinfunction "1_1") (pintype "input"))
      (node (ref "C17") (pin "1") (pinfunction "1_1") (pintype "input"))
      (node (ref "C18") (pin "1") (pinfunction "1_1") (pintype "input"))
      (node (ref "C19") (pin "1") (pinfunction "1_1") (pintype "input"))
      (node (ref "R10") (pin "1") (pinfunction "1_1") (pintype "input"))
      (node (ref "R11") (pin "1") (pinfunction "1_1") (pintype "input"))
      (node (ref "U4") (pin "4") (pinfunction "VSS_4") (pintype "unspecified"))
    )
    (net (code "40") (name "Net-(U5-A0)") (class "Default")
      (node (ref "R18") (pin "1") (pinfunction "1_1") (pintype "input"))
      (node (ref "U5") (pin "2") (pinfunction "A0_2") (pintype "unspecified"))
    )
    (net (code "41") (name "Net-(U5-A1)") (class "Default")
      (node (ref "R17") (pin "1") (pinfunction "1_1") (pintype "input"))
      (node (ref "U5") (pin "1") (pinfunction "A1_1") (pintype "unspecified"))
    )
    (net (code "42") (name "Net-(U5-VIN+)") (class "Default")
      (node (ref "R19") (pin "2") (pinfunction "2_2") (pintype "input"))
      (node (ref "SW2") (pin "1") (pinfunction "1_1") (pintype "unspecified"))
      (node (ref "U5") (pin "10") (pinfunction "VIN+_10") (pintype "unspecified"))
    )
    (net (code "43") (name "Net-(U6-CC1)") (class "Default")
      (node (ref "U6") (pin "7") (pinfunction "CC1_7") (pintype "unspecified"))
      (node (ref "USB1") (pin "A5") (pinfunction "CC1_A5") (pintype "unspecified"))
    )
    (net (code "44") (name "Net-(U6-CC2)") (class "Default")
      (node (ref "U6") (pin "6") (pinfunction "CC2_6") (pintype "unspecified"))
      (node (ref "USB1") (pin "B5") (pinfunction "CC2_B5") (pintype "unspecified"))
    )
    (net (code "45") (name "Net-(U6-DM)") (class "Default")
      (node (ref "U6") (pin "4") (pinfunction "DP_4") (pintype "unspecified"))
      (node (ref "U6") (pin "5") (pinfunction "DM_5") (pintype "unspecified"))
    )
    (net (code "46") (name "Net-(U6-VBUS)") (class "Default")
      (node (ref "R58") (pin "1") (pinfunction "1_1") (pintype "input"))
      (node (ref "U6") (pin "8") (pinfunction "VBUS_8") (pintype "unspecified"))
    )
    (net (code "47") (name "Net-(U6-VDD)") (class "Default")
      (node (ref "C21") (pin "1") (pinfunction "1_1") (pintype "input"))
      (node (ref "R21") (pin "2") (pinfunction "2_2") (pintype "input"))
      (node (ref "R23") (pin "2") (pinfunction "2_2") (pintype "input"))
      (node (ref "U6") (pin "1") (pinfunction "VDD_1") (pintype "unspecified"))
    )
    (net (code "48") (name "Net-(U7-BATT)") (class "Default")
      (node (ref "C23") (pin "1") (pinfunction "1_1") (pintype "input"))
      (node (ref "R24") (pin "2") (pinfunction "2_2") (pintype "input"))
      (node (ref "R51") (pin "1") (pinfunction "1_1") (pintype "input"))
      (node (ref "U7") (pin "10") (pinfunction "BATT_10") (pintype "unspecified"))
    )
    (net (code "49") (name "Net-(U7-BST)") (class "Default")
      (node (ref "C22") (pin "1") (pinfunction "1_1") (pintype "input"))
      (node (ref "U7") (pin "14") (pinfunction "BST_14") (pintype "unspecified"))
    )
    (net (code "50") (name "Net-(U7-COMPI)") (class "Default")
      (node (ref "R52") (pin "2") (pinfunction "2_2") (pintype "input"))
      (node (ref "U7") (pin "9") (pinfunction "COMPI_9") (pintype "unspecified"))
    )
    (net (code "51") (name "Net-(U7-COMPV)") (class "Default")
      (node (ref "R53") (pin "2") (pinfunction "2_2") (pintype "input"))
      (node (ref "U7") (pin "8") (pinfunction "COMPV_8") (pintype "unspecified"))
    )
    (net (code "52") (name "Net-(U7-CSP)") (class "Default")
      (node (ref "L3") (pin "2") (pinfunction "2_2") (pintype "unspecified"))
      (node (ref "R24") (pin "1") (pinfunction "1_1") (pintype "input"))
      (node (ref "U7") (pin "11") (pinfunction "CSP_11") (pintype "unspecified"))
    )
    (net (code "53") (name "Net-(U7-NTC)") (class "Default")
      (node (ref "R56") (pin "2") (pinfunction "2_2") (pintype "input"))
      (node (ref "R57") (pin "1") (pinfunction "1_1") (pintype "input"))
      (node (ref "U7") (pin "2") (pinfunction "NTC_2") (pintype "unspecified"))
    )
    (net (code "54") (name "Net-(U7-TMR)") (class "Default")
      (node (ref "C26") (pin "1") (pinfunction "1_1") (pintype "input"))
      (node (ref "U7") (pin "13") (pinfunction "TMR_13") (pintype "unspecified"))
    )
    (net (code "55") (name "Net-(U7-VREF33)") (class "Default")
      (node (ref "C29") (pin "2") (pinfunction "2_2") (pintype "input"))
      (node (ref "R54") (pin "1") (pinfunction "1_1") (pintype "input"))
      (node (ref "R55") (pin "1") (pinfunction "1_1") (pintype "input"))
      (node (ref "R56") (pin "1") (pinfunction "1_1") (pintype "input"))
      (node (ref "U7") (pin "5") (pinfunction "VREF33_5") (pintype "unspecified"))
    )
    (net (code "56") (name "Net-(U13-FB)") (class "Default")
      (node (ref "R59") (pin "2") (pinfunction "2_2") (pintype "input"))
      (node (ref "R60") (pin "1") (pinfunction "1_1") (pintype "input"))
      (node (ref "U13") (pin "4") (pinfunction "FB_4") (pintype "unspecified"))
    )
    (net (code "57") (name "Net-(U13-OUT)") (class "Default")
      (node (ref "L4") (pin "2") (pinfunction "2_2") (pintype "unspecified"))
      (node (ref "U13") (pin "2") (pinfunction "OUT_2") (pintype "unspecified"))
      (node (ref "U14") (pin "1") (pinfunction "A_1") (pintype "unspecified"))
    )
    (net (code "58") (name "VBAT") (class "Default")
      (node (ref "C10") (pin "1") (pinfunction "1_1") (pintype "input"))
      (node (ref "C11") (pin "1") (pinfunction "1_1") (pintype "input"))
      (node (ref "C12") (pin "1") (pinfunction "1_1") (pintype "input"))
      (node (ref "C3") (pin "1") (pinfunction "1_1") (pintype "input"))
      (node (ref "C30") (pin "1") (pinfunction "1_1") (pintype "input"))
      (node (ref "C4") (pin "1") (pinfunction "1_1") (pintype "input"))
      (node (ref "C5") (pin "1") (pinfunction "1_1") (pintype "input"))
      (node (ref "R1") (pin "2") (pinfunction "2_2") (pintype "input"))
      (node (ref "R19") (pin "1") (pinfunction "1_1") (pintype "input"))
      (node (ref "R51") (pin "2") (pinfunction "2_2") (pintype "input"))
      (node (ref "R7") (pin "2") (pinfunction "2_2") (pintype "input"))
      (node (ref "U1") (pin "3") (pinfunction "VIN_3") (pintype "unspecified"))
      (node (ref "U13") (pin "1") (pinfunction "VIN_1") (pintype "unspecified"))
      (node (ref "U2") (pin "3") (pinfunction "VIN_3") (pintype "unspecified"))
      (node (ref "U5") (pin "8") (pinfunction "VBUS_8") (pintype "unspecified"))
      (node (ref "U5") (pin "9") (pinfunction "VIN-_9") (pintype "unspecified"))
    )
    (net (code "59") (name "VBAT+5V") (class "Default")
      (node (ref "BT3") (pin "2") (pinfunction "2_2") (pintype "input"))
      (node (ref "R14") (pin "1") (pinfunction "1_1") (pintype "input"))
      (node (ref "SW2") (pin "2") (pinfunction "2_2") (pintype "unspecified"))
    )
    (net (code "60") (name "VBUS") (class "Default")
      (node (ref "C27") (pin "1") (pinfunction "1_1") (pintype "input"))
      (node (ref "D2") (pin "2") (pinfunction "A_2") (pintype "unspecified"))
      (node (ref "R21") (pin "1") (pinfunction "1_1") (pintype "input"))
      (node (ref "R58") (pin "2") (pinfunction "2_2") (pintype "input"))
      (node (ref "U7") (pin "1") (pinfunction "VCC_1") (pintype "unspecified"))
      (node (ref "USB1") (pin "A9") (pinfunction "VBUS_A9") (pintype "unspecified"))
      (node (ref "USB1") (pin "B9") (pinfunction "VBUS_B9") (pintype "unspecified"))
    )
    (net (code "61") (name "unconnected-(SW2-Pad3)") (class "Default")
      (node (ref "SW2") (pin "3") (pinfunction "3_3") (pintype "unspecified+no_connect"))
    )
    (net (code "62") (name "unconnected-(SW2-Pad4)") (class "Default")
      (node (ref "SW2") (pin "4") (pinfunction "4_4") (pintype "unspecified+no_connect"))
    )
    (net (code "63") (name "unconnected-(SW2-Pad5)") (class "Default")
      (node (ref "SW2") (pin "5") (pinfunction "5_5") (pintype "unspecified+no_connect"))
    )
    (net (code "64") (name "unconnected-(U6-CFG1-Pad9)") (class "Default")
      (node (ref "U6") (pin "9") (pinfunction "CFG1_9") (pintype "unspecified+no_connect"))
    )
    (net (code "65") (name "unconnected-(U6-CFG2-Pad2)") (class "Default")
      (node (ref "U6") (pin "2") (pinfunction "CFG2_2") (pintype "unspecified+no_connect"))
    )
    (net (code "66") (name "unconnected-(U6-CFG3-Pad3)") (class "Default")
      (node (ref "U6") (pin "3") (pinfunction "CFG3_3") (pintype "unspecified+no_connect"))
    )
    (net (code "67") (name "unconnected-(U7-CELLS-Pad7)") (class "Default")
      (node (ref "U7") (pin "7") (pinfunction "CELLS_7") (pintype "unspecified+no_connect"))
    )
  )
)
